# Lcd.net
KiCad netlist of a schematic drawn in Altium Designer
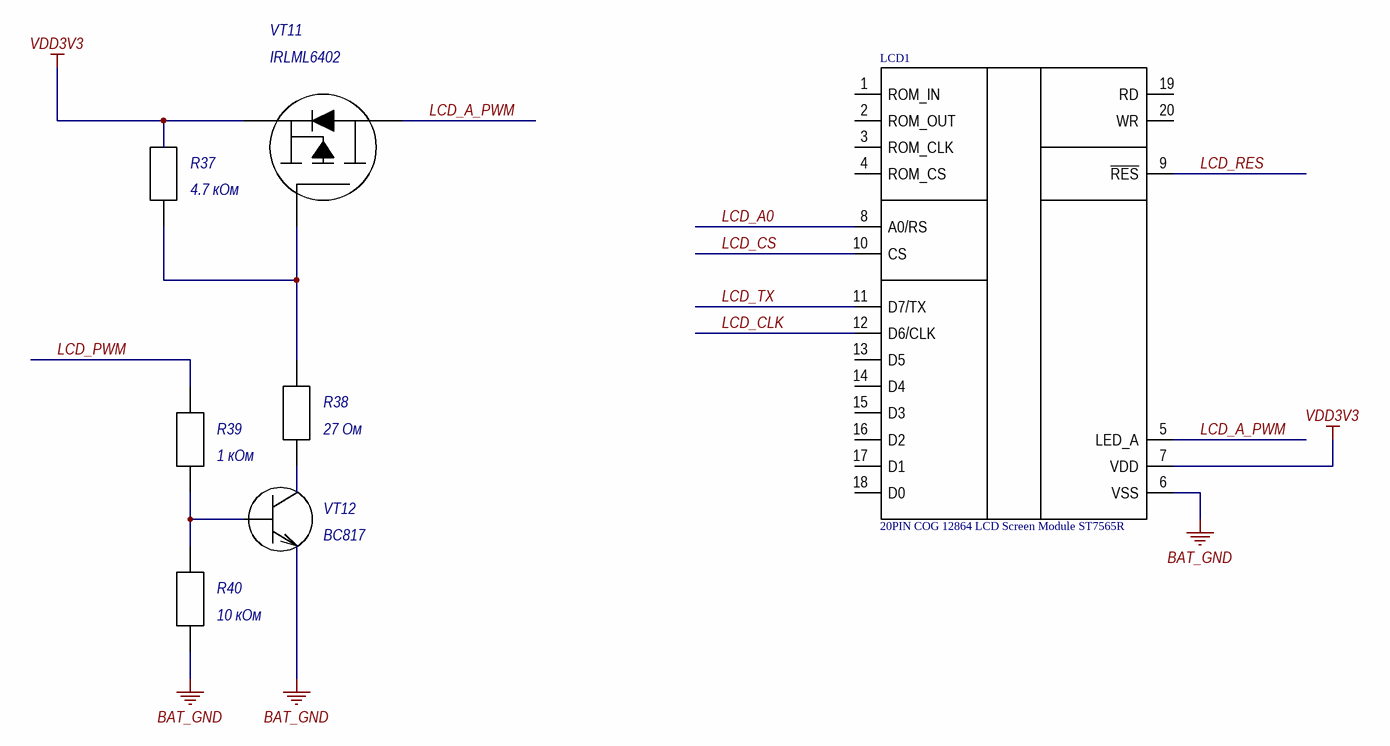
[diagram p0: Lcd.SchDoc]

(export (version "E")
  (design (tool "Eeschema 10.0.6"))
  (components
    (comp (ref "LCD1")
      (value "20PIN COG 12864 LCD Screen Module ST7565R")
      (footprint "COG 12864 LCD Screen Module ST7565R")
      (libsource (lib "my_lib") (part "20PIN COG 12864 LCD Screen Module ST7565R"))
    )
    (comp (ref "R37") (value "4.7 кОм") (footprint "RES 0402") (libsource (lib "my_lib") (part "RES 0402")))
    (comp (ref "R38") (value "27 Ом") (footprint "RES 0402") (libsource (lib "my_lib") (part "RES 0402")))
    (comp (ref "R39") (value "1 кОм") (footprint "RES 0402") (libsource (lib "my_lib") (part "RES 0402")))
    (comp (ref "R40") (value "10 кОм") (footprint "RES 0402") (libsource (lib "my_lib") (part "RES 0402")))
    (comp (ref "VT11") (value "IRLML6402") (footprint "SOT-23") (libsource (lib "my_lib") (part "IRLML6402")))
    (comp (ref "VT12")
      (value "BC817")
      (footprint "SOT-23")
      (description "NPN general-purpose transistor")
      (fields (field (name "MANUFACTURER") "NXP"))
      (libsource (lib "my_lib") (part "BC817"))
    )
  )
  (nets
    (net (code "1") (name "/LCD_A0") (class "Default")
      (node (ref "LCD1") (pin "8") (pinfunction "A0/RS_8") (pintype "passive"))
    )
    (net (code "2") (name "/LCD_A_PWM") (class "Default")
      (node (ref "LCD1") (pin "5") (pinfunction "LED_A_5") (pintype "passive"))
      (node (ref "VT11") (pin "3") (pinfunction "D_3") (pintype "passive"))
    )
    (net (code "3") (name "/LCD_CLK") (class "Default")
      (node (ref "LCD1") (pin "12") (pinfunction "D6/CLK_12") (pintype "passive"))
    )
    (net (code "4") (name "/LCD_CS") (class "Default")
      (node (ref "LCD1") (pin "10") (pinfunction "CS_10") (pintype "passive"))
    )
    (net (code "5") (name "/LCD_PWM") (class "Default")
      (node (ref "R39") (pin "2") (pinfunction "2_2") (pintype "passive"))
    )
    (net (code "6") (name "/LCD_RES") (class "Default")
      (node (ref "LCD1") (pin "9") (pinfunction "~{RES}_9") (pintype "passive"))
    )
    (net (code "7") (name "/LCD_TX") (class "Default")
      (node (ref "LCD1") (pin "11") (pinfunction "D7/TX_11") (pintype "passive"))
    )
    (net (code "8") (name "BAT_GND") (class "Default")
      (node (ref "LCD1") (pin "6") (pinfunction "VSS_6") (pintype "passive"))
      (node (ref "R40") (pin "1") (pinfunction "1_1") (pintype "passive"))
      (node (ref "VT12") (pin "2") (pinfunction "E_2") (pintype "passive"))
    )
    (net (code "9") (name "Net-(VT11-G)") (class "Default")
      (node (ref "R37") (pin "1") (pinfunction "1_1") (pintype "passive"))
      (node (ref "R38") (pin "2") (pinfunction "2_2") (pintype "passive"))
      (node (ref "VT11") (pin "1") (pinfunction "G_1") (pintype "passive"))
    )
    (net (code "10") (name "Net-(VT12-B)") (class "Default")
      (node (ref "R39") (pin "1") (pinfunction "1_1") (pintype "passive"))
      (node (ref "R40") (pin "2") (pinfunction "2_2") (pintype "passive"))
      (node (ref "VT12") (pin "1") (pinfunction "B_1") (pintype "passive"))
    )
    (net (code "11") (name "Net-(VT12-C)") (class "Default")
      (node (ref "R38") (pin "1") (pinfunction "1_1") (pintype "passive"))
      (node (ref "VT12") (pin "3") (pinfunction "C_3") (pintype "passive"))
    )
    (net (code "12") (name "VDD3V3") (class "Default")
      (node (ref "LCD1") (pin "7") (pinfunction "VDD_7") (pintype "passive"))
      (node (ref "R37") (pin "2") (pinfunction "2_2") (pintype "passive"))
      (node (ref "VT11") (pin "2") (pinfunction "S_2") (pintype "passive"))
    )
    (net (code "13") (name "unconnected-(LCD1-D0-Pad18)") (class "Default")
      (node (ref "LCD1") (pin "18") (pinfunction "D0_18") (pintype "passive"))
    )
    (net (code "14") (name "unconnected-(LCD1-D1-Pad17)") (class "Default")
      (node (ref "LCD1") (pin "17") (pinfunction "D1_17") (pintype "passive"))
    )
    (net (code "15") (name "unconnected-(LCD1-D2-Pad16)") (class "Default")
      (node (ref "LCD1") (pin "16") (pinfunction "D2_16") (pintype "passive"))
    )
    (net (code "16") (name "unconnected-(LCD1-D3-Pad15)") (class "Default")
      (node (ref "LCD1") (pin "15") (pinfunction "D3_15") (pintype "passive"))
    )
    (net (code "17") (name "unconnected-(LCD1-D4-Pad14)") (class "Default")
      (node (ref "LCD1") (pin "14") (pinfunction "D4_14") (pintype "passive"))
    )
    (net (code "18") (name "unconnected-(LCD1-D5-Pad13)") (class "Default")
      (node (ref "LCD1") (pin "13") (pinfunction "D5_13") (pintype "passive"))
    )
    (net (code "19") (name "unconnected-(LCD1-RD-Pad19)") (class "Default")
      (node (ref "LCD1") (pin "19") (pinfunction "RD_19") (pintype "passive"))
    )
    (net (code "20") (name "unconnected-(LCD1-ROM_CLK-Pad3)") (class "Default")
      (node (ref "LCD1") (pin "3") (pinfunction "ROM_CLK_3") (pintype "passive"))
    )
    (net (code "21") (name "unconnected-(LCD1-ROM_CS-Pad4)") (class "Default")
      (node (ref "LCD1") (pin "4") (pinfunction "ROM_CS_4") (pintype "passive"))
    )
    (net (code "22") (name "unconnected-(LCD1-ROM_IN-Pad1)") (class "Default")
      (node (ref "LCD1") (pin "1") (pinfunction "ROM_IN_1") (pintype "passive"))
    )
    (net (code "23") (name "unconnected-(LCD1-ROM_OUT-Pad2)") (class "Default")
      (node (ref "LCD1") (pin "2") (pinfunction "ROM_OUT_2") (pintype "passive"))
    )
    (net (code "24") (name "unconnected-(LCD1-WR-Pad20)") (class "Default")
      (node (ref "LCD1") (pin "20") (pinfunction "WR_20") (pintype "passive"))
    )
  )
)
